# attiny_rc_switch_schematic.net
KiCad netlist of a schematic drawn in EAGLE
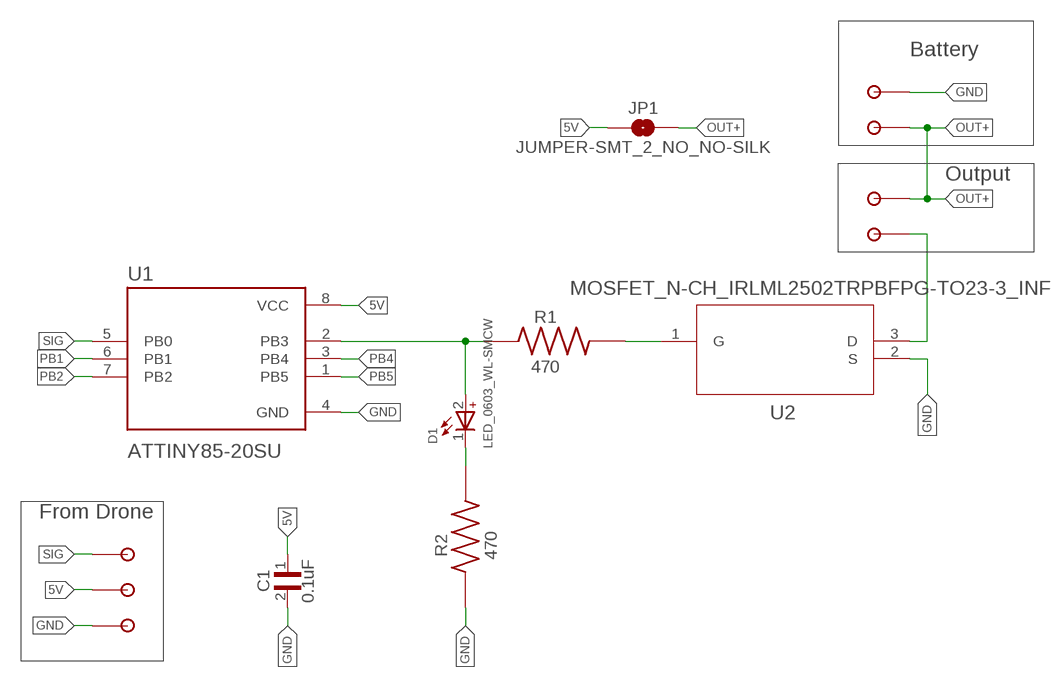
[diagram p0: schematic, sheet 1]

(export (version "E")
  (design (tool "Eeschema 10.0.6"))
  (components
    (comp (ref "C1")
      (value "0.1uF")
      (footprint "eagle-import:CC0603ZRY5V9BB")
      (libsource (lib "eagle-import") (part "CAPACITOR_CERAMIC_0603_50V_CC0603ZRY5V9BB"))
    )
    (comp (ref "D1")
      (value "LED_0603_WL-SMCW")
      (footprint "eagle-import:LED_0603_WL-SMCW")
      (libsource (lib "eagle-import") (part "LED_0603_WL-SMCW"))
    )
    (comp (ref "JP1")
      (value "JUMPER-SMT_2_NO_NO-SILK")
      (footprint "eagle-import:SMT-JUMPER_2_NO_NO-SILK")
      (libsource (lib "eagle-import") (part "JUMPER-SMT_2_NO_NO-SILK"))
    )
    (comp (ref "R1")
      (value "470")
      (footprint "eagle-import:RCS0603")
      (libsource (lib "eagle-import") (part "RESISTOR_0603_1/4W_RCS0603"))
    )
    (comp (ref "R2")
      (value "470")
      (footprint "eagle-import:RCS0603")
      (libsource (lib "eagle-import") (part "RESISTOR_0603_1/4W_RCS0603"))
    )
    (comp (ref "U$1")
      (value "SMD_PAD_NO_STENCIL")
      (footprint "eagle-import:SMD_PAD_NO_STENCIL")
      (libsource (lib "eagle-import") (part "SMD_PAD_NO_STENCIL"))
    )
    (comp (ref "U$2")
      (value "SMD_PAD_NO_STENCIL")
      (footprint "eagle-import:SMD_PAD_NO_STENCIL")
      (libsource (lib "eagle-import") (part "SMD_PAD_NO_STENCIL"))
    )
    (comp (ref "U$3")
      (value "SMD_PAD_NO_STENCIL")
      (footprint "eagle-import:SMD_PAD_NO_STENCIL")
      (libsource (lib "eagle-import") (part "SMD_PAD_NO_STENCIL"))
    )
    (comp (ref "U$4")
      (value "SMD_PAD_NO_STENCIL")
      (footprint "eagle-import:SMD_PAD_NO_STENCIL")
      (libsource (lib "eagle-import") (part "SMD_PAD_NO_STENCIL"))
    )
    (comp (ref "U$5")
      (value "SMD_PAD_NO_STENCIL")
      (footprint "eagle-import:SMD_PAD_NO_STENCIL")
      (libsource (lib "eagle-import") (part "SMD_PAD_NO_STENCIL"))
    )
    (comp (ref "U$6")
      (value "SMD_PAD_NO_STENCIL")
      (footprint "eagle-import:SMD_PAD_NO_STENCIL")
      (libsource (lib "eagle-import") (part "SMD_PAD_NO_STENCIL"))
    )
    (comp (ref "U$7")
      (value "SMD_PAD_NO_STENCIL")
      (footprint "eagle-import:SMD_PAD_NO_STENCIL")
      (libsource (lib "eagle-import") (part "SMD_PAD_NO_STENCIL"))
    )
    (comp (ref "U1")
      (value "ATTINY85-20SU")
      (footprint "eagle-import:ATTINY85-20SU")
      (fields (field (name "MF") "Microchip Technology") (field (name "MP") "ATTINY85V-10SU"))
      (libsource (lib "eagle-import") (part "ATTINY85-20SU"))
    )
    (comp (ref "U2")
      (value "MOSFET_N-CH_IRLML2502TRPBFPG-TO23-3_INF")
      (footprint "eagle-import:MOSFET_N-CH_IRLML2502TRPBF")
      (fields
        (field (name "MANUFACTURER_PART_NUMBER") "IRLML2502TRPBF")
        (field (name "COPYRIGHT") "Copyright (C) 2024 Ultra Librarian. All rights reserved.")
      )
      (libsource (lib "eagle-import") (part "MOSFET_N-CH_IRLML2502TRPBFPG-TO23-3_INF"))
    )
  )
  (nets
    (net (code "1") (name "5V") (class "Default")
      (node (ref "C1") (pin "1") (pinfunction "1_1") (pintype "passive"))
      (node (ref "JP1") (pin "1") (pinfunction "1_1") (pintype "passive"))
      (node (ref "U$2") (pin "P$1") (pinfunction "P$1_P$1") (pintype "bidirectional"))
      (node (ref "U1") (pin "8") (pinfunction "VCC_8") (pintype "power_in"))
    )
    (net (code "2") (name "GND") (class "Default")
      (node (ref "C1") (pin "2") (pinfunction "2_2") (pintype "passive"))
      (node (ref "R2") (pin "1") (pinfunction "1_1") (pintype "passive"))
      (node (ref "U$6") (pin "P$1") (pinfunction "P$1_P$1") (pintype "bidirectional"))
      (node (ref "U$7") (pin "P$1") (pinfunction "P$1_P$1") (pintype "bidirectional"))
      (node (ref "U1") (pin "4") (pinfunction "GND_4") (pintype "power_in"))
      (node (ref "U2") (pin "2") (pinfunction "S_2") (pintype "passive"))
    )
    (net (code "3") (name "Net-(D1-+)") (class "Default")
      (node (ref "D1") (pin "2") (pinfunction "+_2") (pintype "passive"))
      (node (ref "R1") (pin "1") (pinfunction "1_1") (pintype "passive"))
      (node (ref "U1") (pin "2") (pinfunction "PB3_2") (pintype "bidirectional"))
    )
    (net (code "4") (name "Net-(D1--)") (class "Default")
      (node (ref "D1") (pin "1") (pinfunction "-_1") (pintype "passive"))
      (node (ref "R2") (pin "2") (pinfunction "2_2") (pintype "passive"))
    )
    (net (code "5") (name "Net-(U2-D)") (class "Default")
      (node (ref "U$3") (pin "P$1") (pinfunction "P$1_P$1") (pintype "bidirectional"))
      (node (ref "U2") (pin "3") (pinfunction "D_3") (pintype "passive"))
    )
    (net (code "6") (name "Net-(U2-G)") (class "Default")
      (node (ref "R1") (pin "2") (pinfunction "2_2") (pintype "passive"))
      (node (ref "U2") (pin "1") (pinfunction "G_1") (pintype "passive"))
    )
    (net (code "7") (name "OUT+") (class "Default")
      (node (ref "JP1") (pin "2") (pinfunction "2_2") (pintype "passive"))
      (node (ref "U$4") (pin "P$1") (pinfunction "P$1_P$1") (pintype "bidirectional"))
      (node (ref "U$5") (pin "P$1") (pinfunction "P$1_P$1") (pintype "bidirectional"))
    )
    (net (code "8") (name "PB1") (class "Default")
      (node (ref "U1") (pin "6") (pinfunction "PB1_6") (pintype "bidirectional"))
    )
    (net (code "9") (name "PB2") (class "Default")
      (node (ref "U1") (pin "7") (pinfunction "PB2_7") (pintype "bidirectional"))
    )
    (net (code "10") (name "PB4") (class "Default")
      (node (ref "U1") (pin "3") (pinfunction "PB4_3") (pintype "bidirectional"))
    )
    (net (code "11") (name "PB5") (class "Default")
      (node (ref "U1") (pin "1") (pinfunction "PB5_1") (pintype "bidirectional"))
    )
    (net (code "12") (name "SIG") (class "Default")
      (node (ref "U$1") (pin "P$1") (pinfunction "P$1_P$1") (pintype "bidirectional"))
      (node (ref "U1") (pin "5") (pinfunction "PB0_5") (pintype "bidirectional"))
    )
  )
)
